# StormNet18-v0_1.net
KiCad netlist of a schematic drawn in EAGLE
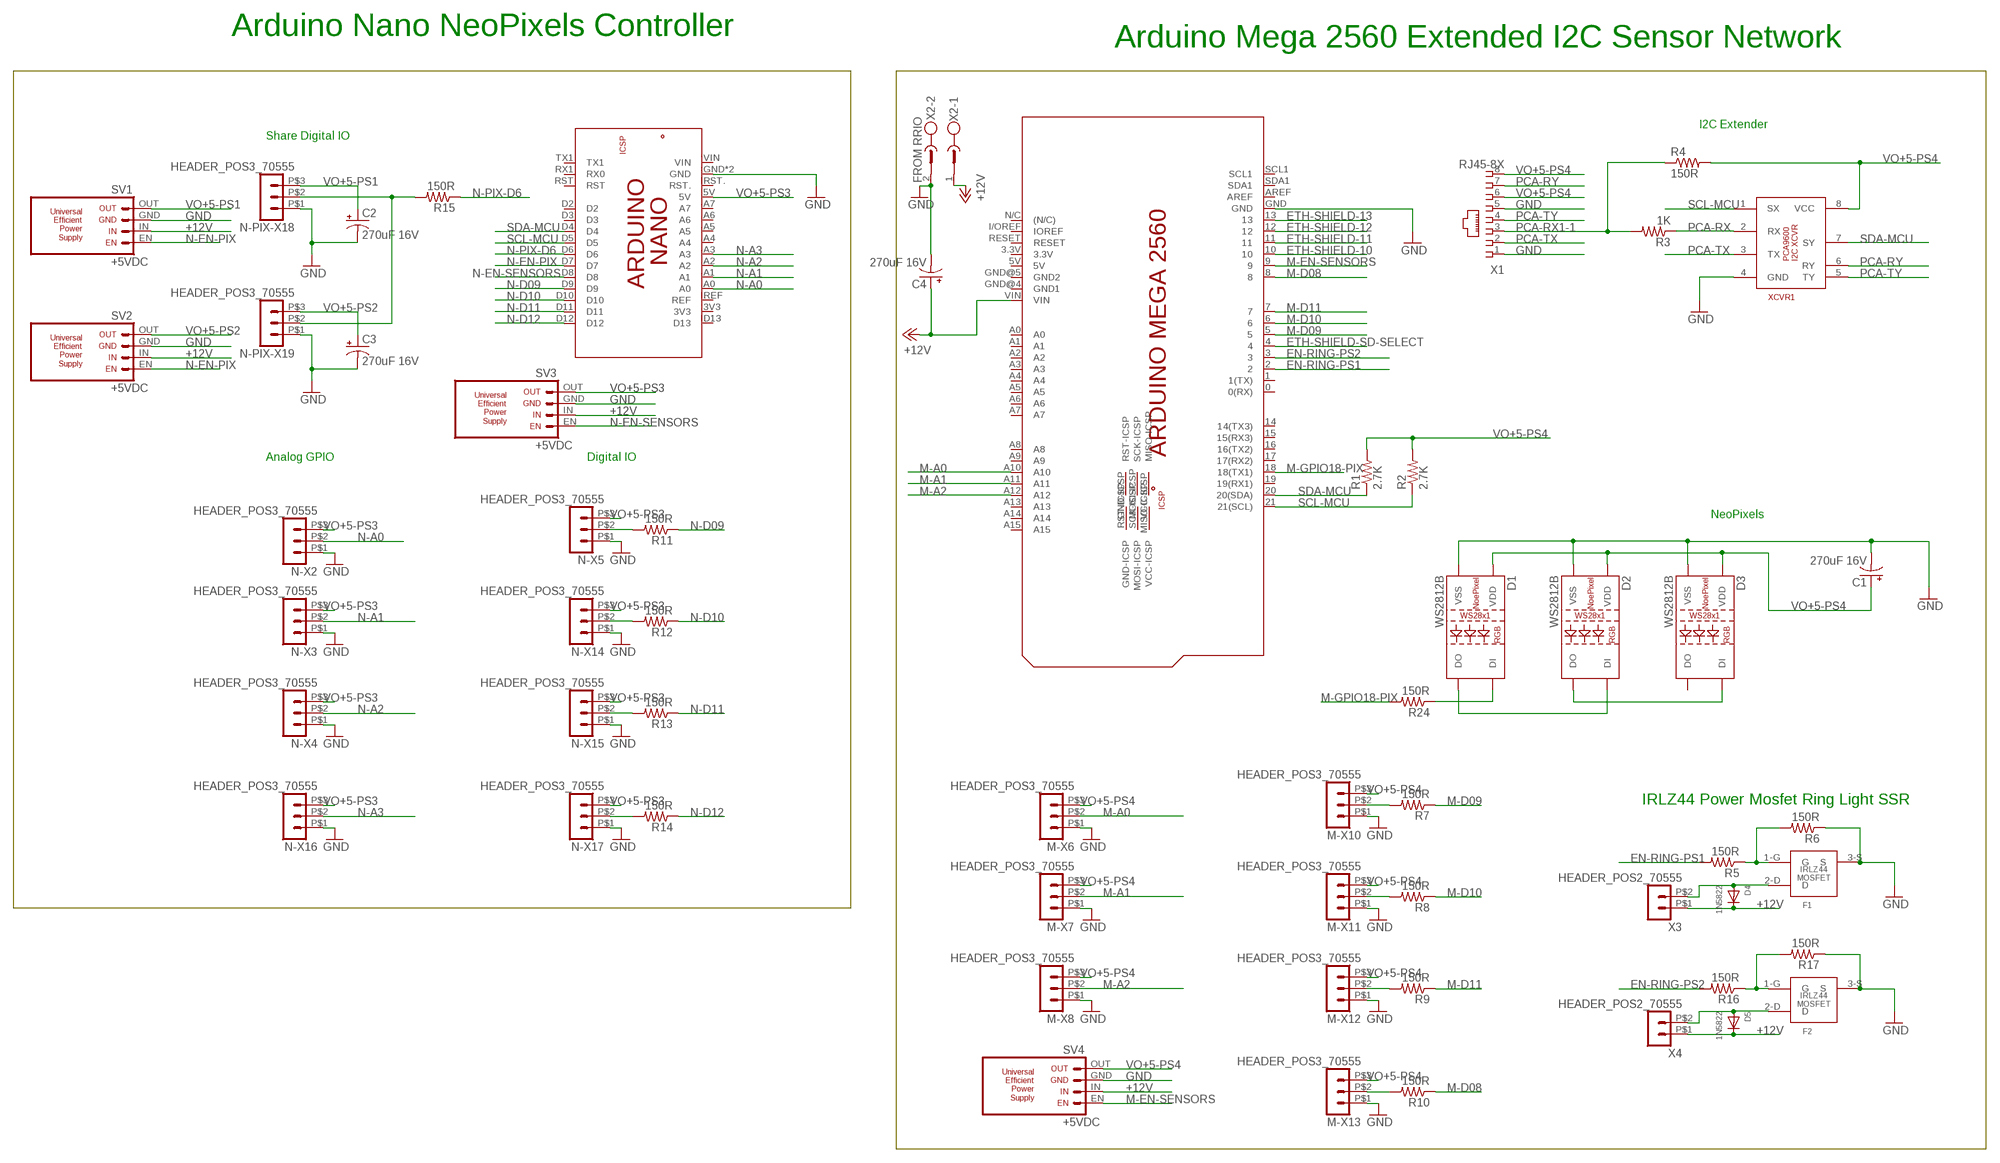
[diagram p0: schematic, sheet 1]

(export (version "E")
  (design (tool "Eeschema 10.0.6"))
  (components
    (comp (ref "C1")
      (value "270uF 16V")
      (footprint "eagle-import:E3,5-8")
      (libsource (lib "eagle-import") (part "CPOL-USE3.5-8"))
    )
    (comp (ref "C2")
      (value "270uF 16V")
      (footprint "eagle-import:E3,5-8")
      (libsource (lib "eagle-import") (part "CPOL-USE3.5-8"))
    )
    (comp (ref "C3")
      (value "270uF 16V")
      (footprint "eagle-import:E3,5-8")
      (libsource (lib "eagle-import") (part "CPOL-USE3.5-8"))
    )
    (comp (ref "C4")
      (value "270uF 16V")
      (footprint "eagle-import:E3,5-8")
      (libsource (lib "eagle-import") (part "CPOL-USE3.5-8"))
    )
    (comp (ref "D1")
      (value "WS2812B")
      (footprint "eagle-import:WS2812B")
      (libsource (lib "eagle-import") (part "WS2812B"))
    )
    (comp (ref "D2")
      (value "WS2812B")
      (footprint "eagle-import:WS2812B")
      (libsource (lib "eagle-import") (part "WS2812B"))
    )
    (comp (ref "D3")
      (value "WS2812B")
      (footprint "eagle-import:WS2812B")
      (libsource (lib "eagle-import") (part "WS2812B"))
    )
    (comp (ref "D4")
      (value "1N5822")
      (footprint "eagle-import:SMADIODE")
      (libsource (lib "eagle-import") (part "DIODESMA"))
    )
    (comp (ref "D5")
      (value "1N5822")
      (footprint "eagle-import:SMADIODE")
      (libsource (lib "eagle-import") (part "DIODESMA"))
    )
    (comp (ref "F1")
      (value "IRLZ44")
      (footprint "eagle-import:IRLZ44-TO220")
      (libsource (lib "eagle-import") (part "IRLZ44"))
    )
    (comp (ref "F2")
      (value "IRLZ44")
      (footprint "eagle-import:IRLZ44-TO220")
      (libsource (lib "eagle-import") (part "IRLZ44"))
    )
    (comp (ref "M-X6")
      (value "HEADER_POS3_70555")
      (footprint "eagle-import:70555-POS3")
      (libsource (lib "eagle-import") (part "HEADER_POS3_?70555"))
    )
    (comp (ref "M-X7")
      (value "HEADER_POS3_70555")
      (footprint "eagle-import:70555-POS3")
      (libsource (lib "eagle-import") (part "HEADER_POS3_?70555"))
    )
    (comp (ref "M-X8")
      (value "HEADER_POS3_70555")
      (footprint "eagle-import:70555-POS3")
      (libsource (lib "eagle-import") (part "HEADER_POS3_?70555"))
    )
    (comp (ref "M-X10")
      (value "HEADER_POS3_70555")
      (footprint "eagle-import:70555-POS3")
      (libsource (lib "eagle-import") (part "HEADER_POS3_?70555"))
    )
    (comp (ref "M-X11")
      (value "HEADER_POS3_70555")
      (footprint "eagle-import:70555-POS3")
      (libsource (lib "eagle-import") (part "HEADER_POS3_?70555"))
    )
    (comp (ref "M-X12")
      (value "HEADER_POS3_70555")
      (footprint "eagle-import:70555-POS3")
      (libsource (lib "eagle-import") (part "HEADER_POS3_?70555"))
    )
    (comp (ref "M-X13")
      (value "HEADER_POS3_70555")
      (footprint "eagle-import:70555-POS3")
      (libsource (lib "eagle-import") (part "HEADER_POS3_?70555"))
    )
    (comp (ref "N-PIX-X18")
      (value "HEADER_POS3_70555")
      (footprint "eagle-import:70555-POS3")
      (libsource (lib "eagle-import") (part "HEADER_POS3_?70555"))
    )
    (comp (ref "N-PIX-X19")
      (value "HEADER_POS3_70555")
      (footprint "eagle-import:70555-POS3")
      (libsource (lib "eagle-import") (part "HEADER_POS3_?70555"))
    )
    (comp (ref "N-X2")
      (value "HEADER_POS3_70555")
      (footprint "eagle-import:70555-POS3")
      (libsource (lib "eagle-import") (part "HEADER_POS3_?70555"))
    )
    (comp (ref "N-X3")
      (value "HEADER_POS3_70555")
      (footprint "eagle-import:70555-POS3")
      (libsource (lib "eagle-import") (part "HEADER_POS3_?70555"))
    )
    (comp (ref "N-X4")
      (value "HEADER_POS3_70555")
      (footprint "eagle-import:70555-POS3")
      (libsource (lib "eagle-import") (part "HEADER_POS3_?70555"))
    )
    (comp (ref "N-X5")
      (value "HEADER_POS3_70555")
      (footprint "eagle-import:70555-POS3")
      (libsource (lib "eagle-import") (part "HEADER_POS3_?70555"))
    )
    (comp (ref "N-X14")
      (value "HEADER_POS3_70555")
      (footprint "eagle-import:70555-POS3")
      (libsource (lib "eagle-import") (part "HEADER_POS3_?70555"))
    )
    (comp (ref "N-X15")
      (value "HEADER_POS3_70555")
      (footprint "eagle-import:70555-POS3")
      (libsource (lib "eagle-import") (part "HEADER_POS3_?70555"))
    )
    (comp (ref "N-X16")
      (value "HEADER_POS3_70555")
      (footprint "eagle-import:70555-POS3")
      (libsource (lib "eagle-import") (part "HEADER_POS3_?70555"))
    )
    (comp (ref "N-X17")
      (value "HEADER_POS3_70555")
      (footprint "eagle-import:70555-POS3")
      (libsource (lib "eagle-import") (part "HEADER_POS3_?70555"))
    )
    (comp (ref "PCB2")
      (value "ARDUINO_MEGA2560_SMALL")
      (footprint "eagle-import:ARDUINO_MEGA2560_SMALL")
      (libsource (lib "eagle-import") (part "ARDUINO_MEGA2560_SMALL"))
    )
    (comp (ref "PCB3")
      (value "ARDUINO_NANOWITHOUT_ICSP")
      (footprint "eagle-import:ARDUINO_NANO")
      (libsource (lib "eagle-import") (part "ARDUINO_NANOWITHOUT_ICSP"))
    )
    (comp (ref "R1")
      (value "2.7K")
      (footprint "eagle-import:R0603")
      (libsource (lib "eagle-import") (part "R-US_R0603"))
    )
    (comp (ref "R2")
      (value "2.7K")
      (footprint "eagle-import:R0603")
      (libsource (lib "eagle-import") (part "R-US_R0603"))
    )
    (comp (ref "R3")
      (value "1K")
      (footprint "eagle-import:R0603")
      (libsource (lib "eagle-import") (part "R-US_R0603"))
    )
    (comp (ref "R4")
      (value "150R")
      (footprint "eagle-import:R0603")
      (libsource (lib "eagle-import") (part "R-US_R0603"))
    )
    (comp (ref "R5")
      (value "150R")
      (footprint "eagle-import:R0603")
      (libsource (lib "eagle-import") (part "R-US_R0603"))
    )
    (comp (ref "R6")
      (value "150R")
      (footprint "eagle-import:R0603")
      (libsource (lib "eagle-import") (part "R-US_R0603"))
    )
    (comp (ref "R7")
      (value "150R")
      (footprint "eagle-import:R0603")
      (libsource (lib "eagle-import") (part "R-US_R0603"))
    )
    (comp (ref "R8")
      (value "150R")
      (footprint "eagle-import:R0603")
      (libsource (lib "eagle-import") (part "R-US_R0603"))
    )
    (comp (ref "R9")
      (value "150R")
      (footprint "eagle-import:R0603")
      (libsource (lib "eagle-import") (part "R-US_R0603"))
    )
    (comp (ref "R10")
      (value "150R")
      (footprint "eagle-import:R0603")
      (libsource (lib "eagle-import") (part "R-US_R0603"))
    )
    (comp (ref "R11")
      (value "150R")
      (footprint "eagle-import:R0603")
      (libsource (lib "eagle-import") (part "R-US_R0603"))
    )
    (comp (ref "R12")
      (value "150R")
      (footprint "eagle-import:R0603")
      (libsource (lib "eagle-import") (part "R-US_R0603"))
    )
    (comp (ref "R13")
      (value "150R")
      (footprint "eagle-import:R0603")
      (libsource (lib "eagle-import") (part "R-US_R0603"))
    )
    (comp (ref "R14")
      (value "150R")
      (footprint "eagle-import:R0603")
      (libsource (lib "eagle-import") (part "R-US_R0603"))
    )
    (comp (ref "R15")
      (value "150R")
      (footprint "eagle-import:R0603")
      (libsource (lib "eagle-import") (part "R-US_R0603"))
    )
    (comp (ref "R16")
      (value "150R")
      (footprint "eagle-import:R0603")
      (libsource (lib "eagle-import") (part "R-US_R0603"))
    )
    (comp (ref "R17")
      (value "150R")
      (footprint "eagle-import:R0603")
      (libsource (lib "eagle-import") (part "R-US_R0603"))
    )
    (comp (ref "R24")
      (value "150R")
      (footprint "eagle-import:R0603")
      (libsource (lib "eagle-import") (part "R-US_R0603"))
    )
    (comp (ref "SV1")
      (value "+5VDC")
      (footprint "eagle-import:PS-UNIV-EFFICIENT-3A")
      (libsource (lib "eagle-import") (part "SUPPLY-UNIV-EFFICIENT"))
    )
    (comp (ref "SV2")
      (value "+5VDC")
      (footprint "eagle-import:PS-UNIV-EFFICIENT-3A")
      (libsource (lib "eagle-import") (part "SUPPLY-UNIV-EFFICIENT"))
    )
    (comp (ref "SV3")
      (value "+5VDC")
      (footprint "eagle-import:PS-UNIV-EFFICIENT-3A")
      (libsource (lib "eagle-import") (part "SUPPLY-UNIV-EFFICIENT"))
    )
    (comp (ref "SV4")
      (value "+5VDC")
      (footprint "eagle-import:PS-UNIV-EFFICIENT-3A")
      (libsource (lib "eagle-import") (part "SUPPLY-UNIV-EFFICIENT"))
    )
    (comp (ref "X1")
      (value "RJ45-8X")
      (footprint "eagle-import:RJ45-NO-SHIELD")
      (libsource (lib "eagle-import") (part "RJ45-8X"))
    )
    (comp (ref "X2")
      (value "FROM RRIO")
      (footprint "eagle-import:MSTBV2-SMALL")
      (libsource (lib "eagle-import") (part "MSTBV2"))
    )
    (comp (ref "X3")
      (value "HEADER_POS2_70555")
      (footprint "eagle-import:70555-POS2")
      (libsource (lib "eagle-import") (part "HEADER_POS2_?70555"))
    )
    (comp (ref "X4")
      (value "HEADER_POS2_70555")
      (footprint "eagle-import:70555-POS2")
      (libsource (lib "eagle-import") (part "HEADER_POS2_?70555"))
    )
    (comp (ref "XCVR1")
      (value "PCA9600DSO8")
      (footprint "eagle-import:SO08")
      (libsource (lib "eagle-import") (part "PCA9600DSO8"))
    )
  )
  (nets
    (net (code "1") (name "+12V") (class "Default")
      (node (ref "C4") (pin "+") (pinfunction "+_+") (pintype "passive"))
      (node (ref "D4") (pin "C") (pinfunction "C_C") (pintype "passive"))
      (node (ref "D5") (pin "C") (pinfunction "C_C") (pintype "passive"))
      (node (ref "PCB2") (pin "VIN") (pinfunction "VIN_VIN") (pintype "power_in"))
      (node (ref "SV1") (pin "IN") (pinfunction "IN_IN") (pintype "passive"))
      (node (ref "SV2") (pin "IN") (pinfunction "IN_IN") (pintype "passive"))
      (node (ref "SV3") (pin "IN") (pinfunction "IN_IN") (pintype "passive"))
      (node (ref "SV4") (pin "IN") (pinfunction "IN_IN") (pintype "passive"))
      (node (ref "X2") (pin "1") (pinfunction "SK_1") (pintype "passive"))
      (node (ref "X3") (pin "P$1") (pinfunction "1_P$1") (pintype "passive"))
      (node (ref "X4") (pin "P$1") (pinfunction "1_P$1") (pintype "passive"))
    )
    (net (code "2") (name "/3.3V") (class "Default")
      (node (ref "PCB2") (pin "3.3V") (pinfunction "3.3V_3.3V") (pintype "power_in"))
    )
    (net (code "3") (name "/5V") (class "Default")
      (node (ref "PCB2") (pin "5V") (pinfunction "5V_5V") (pintype "power_in"))
    )
    (net (code "4") (name "/EN-RING-PS1") (class "Default")
      (node (ref "PCB2") (pin "2") (pinfunction "2_2") (pintype "bidirectional"))
      (node (ref "R5") (pin "2") (pinfunction "2_2") (pintype "passive"))
    )
    (net (code "5") (name "/EN-RING-PS2") (class "Default")
      (node (ref "PCB2") (pin "3") (pinfunction "3_3") (pintype "bidirectional"))
      (node (ref "R16") (pin "2") (pinfunction "2_2") (pintype "passive"))
    )
    (net (code "6") (name "/ETH-SHIELD-10") (class "Default")
      (node (ref "PCB2") (pin "10") (pinfunction "10_10") (pintype "bidirectional"))
    )
    (net (code "7") (name "/ETH-SHIELD-11") (class "Default")
      (node (ref "PCB2") (pin "11") (pinfunction "11_11") (pintype "bidirectional"))
    )
    (net (code "8") (name "/ETH-SHIELD-12") (class "Default")
      (node (ref "PCB2") (pin "12") (pinfunction "12_12") (pintype "bidirectional"))
    )
    (net (code "9") (name "/ETH-SHIELD-13") (class "Default")
      (node (ref "PCB2") (pin "13") (pinfunction "13_13") (pintype "bidirectional"))
    )
    (net (code "10") (name "/ETH-SHIELD-SD-SELECT") (class "Default")
      (node (ref "PCB2") (pin "4") (pinfunction "4_4") (pintype "bidirectional"))
    )
    (net (code "11") (name "/GND1") (class "Default")
      (node (ref "PCB2") (pin "GND@4") (pinfunction "GND1_GND@4") (pintype "power_in"))
    )
    (net (code "12") (name "/GND2") (class "Default")
      (node (ref "PCB2") (pin "GND@5") (pinfunction "GND2_GND@5") (pintype "power_in"))
    )
    (net (code "13") (name "/M-A0") (class "Default")
      (node (ref "M-X6") (pin "P$2") (pinfunction "2_P$2") (pintype "passive"))
      (node (ref "PCB2") (pin "A10") (pinfunction "A10_A10") (pintype "bidirectional"))
    )
    (net (code "14") (name "/M-A1") (class "Default")
      (node (ref "M-X7") (pin "P$2") (pinfunction "2_P$2") (pintype "passive"))
      (node (ref "PCB2") (pin "A11") (pinfunction "A11_A11") (pintype "bidirectional"))
    )
    (net (code "15") (name "/M-A2") (class "Default")
      (node (ref "M-X8") (pin "P$2") (pinfunction "2_P$2") (pintype "passive"))
      (node (ref "PCB2") (pin "A12") (pinfunction "A12_A12") (pintype "bidirectional"))
    )
    (net (code "16") (name "/M-D08") (class "Default")
      (node (ref "PCB2") (pin "8") (pinfunction "8_8") (pintype "bidirectional"))
      (node (ref "R10") (pin "1") (pinfunction "1_1") (pintype "passive"))
    )
    (net (code "17") (name "/M-D09") (class "Default")
      (node (ref "PCB2") (pin "5") (pinfunction "5_5") (pintype "bidirectional"))
      (node (ref "R7") (pin "1") (pinfunction "1_1") (pintype "passive"))
    )
    (net (code "18") (name "/M-D10") (class "Default")
      (node (ref "PCB2") (pin "6") (pinfunction "6_6") (pintype "bidirectional"))
      (node (ref "R8") (pin "1") (pinfunction "1_1") (pintype "passive"))
    )
    (net (code "19") (name "/M-D11") (class "Default")
      (node (ref "PCB2") (pin "7") (pinfunction "7_7") (pintype "bidirectional"))
      (node (ref "R9") (pin "1") (pinfunction "1_1") (pintype "passive"))
    )
    (net (code "20") (name "/M-EN-SENSORS") (class "Default")
      (node (ref "PCB2") (pin "9") (pinfunction "9_9") (pintype "bidirectional"))
      (node (ref "SV4") (pin "EN") (pinfunction "EN_EN") (pintype "passive"))
    )
    (net (code "21") (name "/M-GPIO18-PIX") (class "Default")
      (node (ref "PCB2") (pin "18") (pinfunction "18(TX1)_18") (pintype "bidirectional"))
      (node (ref "R24") (pin "2") (pinfunction "2_2") (pintype "passive"))
    )
    (net (code "22") (name "/N-A0") (class "Default")
      (node (ref "N-X2") (pin "P$2") (pinfunction "2_P$2") (pintype "passive"))
      (node (ref "PCB3") (pin "A0") (pinfunction "A0_A0") (pintype "bidirectional"))
    )
    (net (code "23") (name "/N-A1") (class "Default")
      (node (ref "N-X3") (pin "P$2") (pinfunction "2_P$2") (pintype "passive"))
      (node (ref "PCB3") (pin "A1") (pinfunction "A1_A1") (pintype "bidirectional"))
    )
    (net (code "24") (name "/N-A2") (class "Default")
      (node (ref "N-X4") (pin "P$2") (pinfunction "2_P$2") (pintype "passive"))
      (node (ref "PCB3") (pin "A2") (pinfunction "A2_A2") (pintype "bidirectional"))
    )
    (net (code "25") (name "/N-A3") (class "Default")
      (node (ref "N-X16") (pin "P$2") (pinfunction "2_P$2") (pintype "passive"))
      (node (ref "PCB3") (pin "A3") (pinfunction "A3_A3") (pintype "bidirectional"))
    )
    (net (code "26") (name "/N-D09") (class "Default")
      (node (ref "PCB3") (pin "D9") (pinfunction "D9_D9") (pintype "bidirectional"))
      (node (ref "R11") (pin "1") (pinfunction "1_1") (pintype "passive"))
    )
    (net (code "27") (name "/N-D10") (class "Default")
      (node (ref "PCB3") (pin "D10") (pinfunction "D10_D10") (pintype "bidirectional"))
      (node (ref "R12") (pin "1") (pinfunction "1_1") (pintype "passive"))
    )
    (net (code "28") (name "/N-D11") (class "Default")
      (node (ref "PCB3") (pin "D11") (pinfunction "D11_D11") (pintype "bidirectional"))
      (node (ref "R13") (pin "1") (pinfunction "1_1") (pintype "passive"))
    )
    (net (code "29") (name "/N-D12") (class "Default")
      (node (ref "PCB3") (pin "D12") (pinfunction "D12_D12") (pintype "bidirectional"))
      (node (ref "R14") (pin "1") (pinfunction "1_1") (pintype "passive"))
    )
    (net (code "30") (name "/N-EN-PIX") (class "Default")
      (node (ref "PCB3") (pin "D7") (pinfunction "D7_D7") (pintype "bidirectional"))
      (node (ref "SV1") (pin "EN") (pinfunction "EN_EN") (pintype "passive"))
      (node (ref "SV2") (pin "EN") (pinfunction "EN_EN") (pintype "passive"))
    )
    (net (code "31") (name "/N-EN-SENSORS") (class "Default")
      (node (ref "PCB3") (pin "D8") (pinfunction "D8_D8") (pintype "bidirectional"))
      (node (ref "SV3") (pin "EN") (pinfunction "EN_EN") (pintype "passive"))
    )
    (net (code "32") (name "/N-PIX-D6") (class "Default")
      (node (ref "PCB3") (pin "D6") (pinfunction "D6_D6") (pintype "bidirectional"))
      (node (ref "R15") (pin "1") (pinfunction "1_1") (pintype "passive"))
    )
    (net (code "33") (name "/PCA-RX") (class "Default")
      (node (ref "R3") (pin "1") (pinfunction "1_1") (pintype "passive"))
      (node (ref "XCVR1") (pin "2") (pinfunction "RX_2") (pintype "bidirectional"))
    )
    (net (code "34") (name "/PCA-RX1-1") (class "Default")
      (node (ref "R3") (pin "2") (pinfunction "2_2") (pintype "passive"))
      (node (ref "R4") (pin "1") (pinfunction "1_1") (pintype "passive"))
      (node (ref "X1") (pin "3") (pinfunction "3_3") (pintype "passive"))
    )
    (net (code "35") (name "/PCA-RY") (class "Default")
      (node (ref "X1") (pin "7") (pinfunction "7_7") (pintype "passive"))
      (node (ref "XCVR1") (pin "6") (pinfunction "RY_6") (pintype "bidirectional"))
    )
    (net (code "36") (name "/PCA-TX") (class "Default")
      (node (ref "X1") (pin "2") (pinfunction "2_2") (pintype "passive"))
      (node (ref "XCVR1") (pin "3") (pinfunction "TX_3") (pintype "bidirectional"))
    )
    (net (code "37") (name "/PCA-TY") (class "Default")
      (node (ref "X1") (pin "4") (pinfunction "4_4") (pintype "passive"))
      (node (ref "XCVR1") (pin "5") (pinfunction "TY_5") (pintype "bidirectional"))
    )
    (net (code "38") (name "/SCL-MCU") (class "Default")
      (node (ref "PCB2") (pin "21") (pinfunction "21(SCL)_21") (pintype "bidirectional"))
      (node (ref "PCB3") (pin "D5") (pinfunction "D5_D5") (pintype "bidirectional"))
      (node (ref "R2") (pin "1") (pinfunction "1_1") (pintype "passive"))
      (node (ref "XCVR1") (pin "1") (pinfunction "SX_1") (pintype "bidirectional"))
    )
    (net (code "39") (name "/SDA-MCU") (class "Default")
      (node (ref "PCB2") (pin "20") (pinfunction "20(SDA)_20") (pintype "bidirectional"))
      (node (ref "PCB3") (pin "D4") (pinfunction "D4_D4") (pintype "bidirectional"))
      (node (ref "R1") (pin "1") (pinfunction "1_1") (pintype "passive"))
      (node (ref "XCVR1") (pin "7") (pinfunction "SY_7") (pintype "bidirectional"))
    )
    (net (code "40") (name "/VO+5-PS1") (class "Default")
      (node (ref "C2") (pin "+") (pinfunction "+_+") (pintype "passive"))
      (node (ref "N-PIX-X18") (pin "P$3") (pinfunction "3_P$3") (pintype "passive"))
      (node (ref "SV1") (pin "OUT") (pinfunction "OUT_OUT") (pintype "passive"))
    )
    (net (code "41") (name "/VO+5-PS2") (class "Default")
      (node (ref "C3") (pin "+") (pinfunction "+_+") (pintype "passive"))
      (node (ref "N-PIX-X19") (pin "P$3") (pinfunction "3_P$3") (pintype "passive"))
      (node (ref "SV2") (pin "OUT") (pinfunction "OUT_OUT") (pintype "passive"))
    )
    (net (code "42") (name "/VO+5-PS3") (class "Default")
      (node (ref "N-X14") (pin "P$3") (pinfunction "3_P$3") (pintype "passive"))
      (node (ref "N-X15") (pin "P$3") (pinfunction "3_P$3") (pintype "passive"))
      (node (ref "N-X16") (pin "P$3") (pinfunction "3_P$3") (pintype "passive"))
      (node (ref "N-X17") (pin "P$3") (pinfunction "3_P$3") (pintype "passive"))
      (node (ref "N-X2") (pin "P$3") (pinfunction "3_P$3") (pintype "passive"))
      (node (ref "N-X3") (pin "P$3") (pinfunction "3_P$3") (pintype "passive"))
      (node (ref "N-X4") (pin "P$3") (pinfunction "3_P$3") (pintype "passive"))
      (node (ref "N-X5") (pin "P$3") (pinfunction "3_P$3") (pintype "passive"))
      (node (ref "PCB3") (pin "5V") (pinfunction "5V_5V") (pintype "bidirectional"))
      (node (ref "SV3") (pin "OUT") (pinfunction "OUT_OUT") (pintype "passive"))
    )
    (net (code "43") (name "/VO+5-PS4") (class "Default")
      (node (ref "C1") (pin "+") (pinfunction "+_+") (pintype "passive"))
      (node (ref "D1") (pin "1") (pinfunction "VDD_1") (pintype "bidirectional"))
      (node (ref "D2") (pin "1") (pinfunction "VDD_1") (pintype "bidirectional"))
      (node (ref "D3") (pin "1") (pinfunction "VDD_1") (pintype "bidirectional"))
      (node (ref "M-X10") (pin "P$3") (pinfunction "3_P$3") (pintype "passive"))
      (node (ref "M-X11") (pin "P$3") (pinfunction "3_P$3") (pintype "passive"))
      (node (ref "M-X12") (pin "P$3") (pinfunction "3_P$3") (pintype "passive"))
      (node (ref "M-X13") (pin "P$3") (pinfunction "3_P$3") (pintype "passive"))
      (node (ref "M-X6") (pin "P$3") (pinfunction "3_P$3") (pintype "passive"))
      (node (ref "M-X7") (pin "P$3") (pinfunction "3_P$3") (pintype "passive"))
      (node (ref "M-X8") (pin "P$3") (pinfunction "3_P$3") (pintype "passive"))
      (node (ref "R1") (pin "2") (pinfunction "2_2") (pintype "passive"))
      (node (ref "R2") (pin "2") (pinfunction "2_2") (pintype "passive"))
      (node (ref "R4") (pin "2") (pinfunction "2_2") (pintype "passive"))
      (node (ref "SV4") (pin "OUT") (pinfunction "OUT_OUT") (pintype "passive"))
      (node (ref "X1") (pin "6") (pinfunction "6_6") (pintype "passive"))
      (node (ref "X1") (pin "8") (pinfunction "8_8") (pintype "passive"))
      (node (ref "XCVR1") (pin "8") (pinfunction "VCC_8") (pintype "bidirectional"))
    )
    (net (code "44") (name "GND") (class "Default")
      (node (ref "C1") (pin "-") (pinfunction "-_-") (pintype "passive"))
      (node (ref "C2") (pin "-") (pinfunction "-_-") (pintype "passive"))
      (node (ref "C3") (pin "-") (pinfunction "-_-") (pintype "passive"))
      (node (ref "C4") (pin "-") (pinfunction "-_-") (pintype "passive"))
      (node (ref "D1") (pin "3") (pinfunction "VSS_3") (pintype "bidirectional"))
      (node (ref "D2") (pin "3") (pinfunction "VSS_3") (pintype "bidirectional"))
      (node (ref "D3") (pin "3") (pinfunction "VSS_3") (pintype "bidirectional"))
      (node (ref "F1") (pin "3-S") (pinfunction "S_3-S") (pintype "bidirectional"))
      (node (ref "F2") (pin "3-S") (pinfunction "S_3-S") (pintype "bidirectional"))
      (node (ref "M-X10") (pin "P$1") (pinfunction "1_P$1") (pintype "passive"))
      (node (ref "M-X11") (pin "P$1") (pinfunction "1_P$1") (pintype "passive"))
      (node (ref "M-X12") (pin "P$1") (pinfunction "1_P$1") (pintype "passive"))
      (node (ref "M-X13") (pin "P$1") (pinfunction "1_P$1") (pintype "passive"))
      (node (ref "M-X6") (pin "P$1") (pinfunction "1_P$1") (pintype "passive"))
      (node (ref "M-X7") (pin "P$1") (pinfunction "1_P$1") (pintype "passive"))
      (node (ref "M-X8") (pin "P$1") (pinfunction "1_P$1") (pintype "passive"))
      (node (ref "N-PIX-X18") (pin "P$1") (pinfunction "1_P$1") (pintype "passive"))
      (node (ref "N-PIX-X19") (pin "P$1") (pinfunction "1_P$1") (pintype "passive"))
      (node (ref "N-X14") (pin "P$1") (pinfunction "1_P$1") (pintype "passive"))
      (node (ref "N-X15") (pin "P$1") (pinfunction "1_P$1") (pintype "passive"))
      (node (ref "N-X16") (pin "P$1") (pinfunction "1_P$1") (pintype "passive"))
      (node (ref "N-X17") (pin "P$1") (pinfunction "1_P$1") (pintype "passive"))
      (node (ref "N-X2") (pin "P$1") (pinfunction "1_P$1") (pintype "passive"))
      (node (ref "N-X3") (pin "P$1") (pinfunction "1_P$1") (pintype "passive"))
      (node (ref "N-X4") (pin "P$1") (pinfunction "1_P$1") (pintype "passive"))
      (node (ref "N-X5") (pin "P$1") (pinfunction "1_P$1") (pintype "passive"))
      (node (ref "PCB2") (pin "GND") (pinfunction "GND_GND") (pintype "power_in"))
      (node (ref "PCB3") (pin "GND") (pinfunction "GND_GND") (pintype "bidirectional"))
      (node (ref "PCB3") (pin "GND@1") (pinfunction "GND_GND@1") (pintype "bidirectional"))
      (node (ref "R17") (pin "1") (pinfunction "1_1") (pintype "passive"))
      (node (ref "R6") (pin "1") (pinfunction "1_1") (pintype "passive"))
      (node (ref "SV1") (pin "GND") (pinfunction "GND_GND") (pintype "passive"))
      (node (ref "SV2") (pin "GND") (pinfunction "GND_GND") (pintype "passive"))
      (node (ref "SV3") (pin "GND") (pinfunction "GND_GND") (pintype "passive"))
      (node (ref "SV4") (pin "GND") (pinfunction "GND_GND") (pintype "passive"))
      (node (ref "X1") (pin "1") (pinfunction "1_1") (pintype "passive"))
      (node (ref "X1") (pin "5") (pinfunction "5_5") (pintype "passive"))
      (node (ref "X2") (pin "2") (pinfunction "SK_2") (pintype "passive"))
      (node (ref "XCVR1") (pin "4") (pinfunction "GND_4") (pintype "bidirectional"))
    )
    (net (code "45") (name "Net-(D1-DI)") (class "Default")
      (node (ref "D1") (pin "4") (pinfunction "DI_4") (pintype "bidirectional"))
      (node (ref "R24") (pin "1") (pinfunction "1_1") (pintype "passive"))
    )
    (net (code "46") (name "Net-(D1-DO)") (class "Default")
      (node (ref "D1") (pin "2") (pinfunction "DO_2") (pintype "bidirectional"))
      (node (ref "D2") (pin "4") (pinfunction "DI_4") (pintype "bidirectional"))
    )
    (net (code "47") (name "Net-(D2-DO)") (class "Default")
      (node (ref "D2") (pin "2") (pinfunction "DO_2") (pintype "bidirectional"))
      (node (ref "D3") (pin "4") (pinfunction "DI_4") (pintype "bidirectional"))
    )
    (net (code "48") (name "Net-(F1-D)") (class "Default")
      (node (ref "D4") (pin "A") (pinfunction "A_A") (pintype "passive"))
      (node (ref "F1") (pin "2-D") (pinfunction "D_2-D") (pintype "bidirectional"))
      (node (ref "X3") (pin "P$2") (pinfunction "2_P$2") (pintype "passive"))
    )
    (net (code "49") (name "Net-(F1-G)") (class "Default")
      (node (ref "F1") (pin "1-G") (pinfunction "G_1-G") (pintype "bidirectional"))
      (node (ref "R5") (pin "1") (pinfunction "1_1") (pintype "passive"))
      (node (ref "R6") (pin "2") (pinfunction "2_2") (pintype "passive"))
    )
    (net (code "50") (name "Net-(F2-D)") (class "Default")
      (node (ref "D5") (pin "A") (pinfunction "A_A") (pintype "passive"))
      (node (ref "F2") (pin "2-D") (pinfunction "D_2-D") (pintype "bidirectional"))
      (node (ref "X4") (pin "P$2") (pinfunction "2_P$2") (pintype "passive"))
    )
    (net (code "51") (name "Net-(F2-G)") (class "Default")
      (node (ref "F2") (pin "1-G") (pinfunction "G_1-G") (pintype "bidirectional"))
      (node (ref "R16") (pin "1") (pinfunction "1_1") (pintype "passive"))
      (node (ref "R17") (pin "2") (pinfunction "2_2") (pintype "passive"))
    )
    (net (code "52") (name "Net-(M-X10-2)") (class "Default")
      (node (ref "M-X10") (pin "P$2") (pinfunction "2_P$2") (pintype "passive"))
      (node (ref "R7") (pin "2") (pinfunction "2_2") (pintype "passive"))
    )
    (net (code "53") (name "Net-(M-X11-2)") (class "Default")
      (node (ref "M-X11") (pin "P$2") (pinfunction "2_P$2") (pintype "passive"))
      (node (ref "R8") (pin "2") (pinfunction "2_2") (pintype "passive"))
    )
    (net (code "54") (name "Net-(M-X12-2)") (class "Default")
      (node (ref "M-X12") (pin "P$2") (pinfunction "2_P$2") (pintype "passive"))
      (node (ref "R9") (pin "2") (pinfunction "2_2") (pintype "passive"))
    )
    (net (code "55") (name "Net-(M-X13-2)") (class "Default")
      (node (ref "M-X13") (pin "P$2") (pinfunction "2_P$2") (pintype "passive"))
      (node (ref "R10") (pin "2") (pinfunction "2_2") (pintype "passive"))
    )
    (net (code "56") (name "Net-(N-PIX-X18-2)") (class "Default")
      (node (ref "N-PIX-X18") (pin "P$2") (pinfunction "2_P$2") (pintype "passive"))
      (node (ref "N-PIX-X19") (pin "P$2") (pinfunction "2_P$2") (pintype "passive"))
      (node (ref "R15") (pin "2") (pinfunction "2_2") (pintype "passive"))
    )
    (net (code "57") (name "Net-(N-X5-2)") (class "Default")
      (node (ref "N-X5") (pin "P$2") (pinfunction "2_P$2") (pintype "passive"))
      (node (ref "R11") (pin "2") (pinfunction "2_2") (pintype "passive"))
    )
    (net (code "58") (name "Net-(N-X14-2)") (class "Default")
      (node (ref "N-X14") (pin "P$2") (pinfunction "2_P$2") (pintype "passive"))
      (node (ref "R12") (pin "2") (pinfunction "2_2") (pintype "passive"))
    )
    (net (code "59") (name "Net-(N-X15-2)") (class "Default")
      (node (ref "N-X15") (pin "P$2") (pinfunction "2_P$2") (pintype "passive"))
      (node (ref "R13") (pin "2") (pinfunction "2_2") (pintype "passive"))
    )
    (net (code "60") (name "Net-(N-X17-2)") (class "Default")
      (node (ref "N-X17") (pin "P$2") (pinfunction "2_P$2") (pintype "passive"))
      (node (ref "R14") (pin "2") (pinfunction "2_2") (pintype "passive"))
    )
    (net (code "61") (name "unconnected-(D3-DO-Pad2)") (class "Default")
      (node (ref "D3") (pin "2") (pinfunction "DO_2") (pintype "bidirectional"))
    )
    (net (code "62") (name "unconnected-(PCB2-(N{slash}C)-PadN{slash}C)") (class "Default")
      (node (ref "PCB2") (pin "N/C") (pinfunction "(N/C)_N/C") (pintype "no_connect"))
    )
    (net (code "63") (name "unconnected-(PCB2-0(RX)-Pad0)") (class "Default")
      (node (ref "PCB2") (pin "0") (pinfunction "0(RX)_0") (pintype "bidirectional"))
    )
    (net (code "64") (name "unconnected-(PCB2-1(TX)-Pad1)") (class "Default")
      (node (ref "PCB2") (pin "1") (pinfunction "1(TX)_1") (pintype "bidirectional"))
    )
    (net (code "65") (name "unconnected-(PCB2-14(TX3)-Pad14)") (class "Default")
      (node (ref "PCB2") (pin "14") (pinfunction "14(TX3)_14") (pintype "bidirectional"))
    )
    (net (code "66") (name "unconnected-(PCB2-15(RX3)-Pad15)") (class "Default")
      (node (ref "PCB2") (pin "15") (pinfunction "15(RX3)_15") (pintype "bidirectional"))
    )
    (net (code "67") (name "unconnected-(PCB2-16(TX2)-Pad16)") (class "Default")
      (node (ref "PCB2") (pin "16") (pinfunction "16(TX2)_16") (pintype "bidirectional"))
    )
    (net (code "68") (name "unconnected-(PCB2-17(RX2)-Pad17)") (class "Default")
      (node (ref "PCB2") (pin "17") (pinfunction "17(RX2)_17") (pintype "bidirectional"))
    )
    (net (code "69") (name "unconnected-(PCB2-19(RX1)-Pad19)") (class "Default")
      (node (ref "PCB2") (pin "19") (pinfunction "19(RX1)_19") (pintype "bidirectional"))
    )
    (net (code "70") (name "unconnected-(PCB2-IOREF-PadI{slash}OREF)") (class "Default")
      (node (ref "PCB2") (pin "I/OREF") (pinfunction "IOREF_I/OREF") (pintype "bidirectional"))
    )
    (net (code "71") (name "unconnected-(PCB2-PadA0)") (class "Default")
      (node (ref "PCB2") (pin "A0") (pinfunction "A0_A0") (pintype "bidirectional"))
    )
    (net (code "72") (name "unconnected-(PCB2-PadA1)") (class "Default")
      (node (ref "PCB2") (pin "A1") (pinfunction "A1_A1") (pintype "bidirectional"))
    )
    (net (code "73") (name "unconnected-(PCB2-PadA2)") (class "Default")
      (node (ref "PCB2") (pin "A2") (pinfunction "A2_A2") (pintype "bidirectional"))
    )
    (net (code "74") (name "unconnected-(PCB2-PadA3)") (class "Default")
      (node (ref "PCB2") (pin "A3") (pinfunction "A3_A3") (pintype "bidirectional"))
    )
    (net (code "75") (name "unconnected-(PCB2-PadA4)") (class "Default")
      (node (ref "PCB2") (pin "A4") (pinfunction "A4_A4") (pintype "bidirectional"))
    )
    (net (code "76") (name "unconnected-(PCB2-PadA5)") (class "Default")
      (node (ref "PCB2") (pin "A5") (pinfunction "A5_A5") (pintype "bidirectional"))
    )
    (net (code "77") (name "unconnected-(PCB2-PadA6)") (class "Default")
      (node (ref "PCB2") (pin "A6") (pinfunction "A6_A6") (pintype "bidirectional"))
    )
    (net (code "78") (name "unconnected-(PCB2-PadA7)") (class "Default")
      (node (ref "PCB2") (pin "A7") (pinfunction "A7_A7") (pintype "bidirectional"))
    )
    (net (code "79") (name "unconnected-(PCB2-PadA8)") (class "Default")
      (node (ref "PCB2") (pin "A8") (pinfunction "A8_A8") (pintype "bidirectional"))
    )
    (net (code "80") (name "unconnected-(PCB2-PadA9)") (class "Default")
      (node (ref "PCB2") (pin "A9") (pinfunction "A9_A9") (pintype "bidirectional"))
    )
    (net (code "81") (name "unconnected-(PCB2-PadA13)") (class "Default")
      (node (ref "PCB2") (pin "A13") (pinfunction "A13_A13") (pintype "bidirectional"))
    )
    (net (code "82") (name "unconnected-(PCB2-PadA14)") (class "Default")
      (node (ref "PCB2") (pin "A14") (pinfunction "A14_A14") (pintype "bidirectional"))
    )
    (net (code "83") (name "unconnected-(PCB2-PadA15)") (class "Default")
      (node (ref "PCB2") (pin "A15") (pinfunction "A15_A15") (pintype "bidirectional"))
    )
    (net (code "84") (name "unconnected-(PCB2-PadAREF)") (class "Default")
      (node (ref "PCB2") (pin "AREF") (pinfunction "AREF_AREF") (pintype "bidirectional"))
    )
    (net (code "85") (name "unconnected-(PCB2-PadGND-ICSP)") (class "Default")
      (node (ref "PCB2") (pin "GND-ICSP") (pinfunction "GND-ICSP_GND-ICSP") (pintype "bidirectional"))
    )
    (net (code "86") (name "unconnected-(PCB2-PadMISO-ICSP)") (class "Default")
      (node (ref "PCB2") (pin "MISO-ICSP") (pinfunction "MISO-ICSP_MISO-ICSP") (pintype "bidirectional"))
    )
    (net (code "87") (name "unconnected-(PCB2-PadMOSI-ICSP)") (class "Default")
      (node (ref "PCB2") (pin "MOSI-ICSP") (pinfunction "MOSI-ICSP_MOSI-ICSP") (pintype "bidirectional"))
    )
    (net (code "88") (name "unconnected-(PCB2-PadRESET)") (class "Default")
      (node (ref "PCB2") (pin "RESET") (pinfunction "RESET_RESET") (pintype "input"))
    )
    (net (code "89") (name "unconnected-(PCB2-PadRST-ICSP)") (class "Default")
      (node (ref "PCB2") (pin "RST-ICSP") (pinfunction "RST-ICSP_RST-ICSP") (pintype "bidirectional"))
    )
    (net (code "90") (name "unconnected-(PCB2-PadSCK-ICSP)") (class "Default")
      (node (ref "PCB2") (pin "SCK-ICSP") (pinfunction "SCK-ICSP_SCK-ICSP") (pintype "bidirectional"))
    )
    (net (code "91") (name "unconnected-(PCB2-PadSCL1)") (class "Default")
      (node (ref "PCB2") (pin "SCL1") (pinfunction "SCL1_SCL1") (pintype "bidirectional"))
    )
    (net (code "92") (name "unconnected-(PCB2-PadSDA1)") (class "Default")
      (node (ref "PCB2") (pin "SDA1") (pinfunction "SDA1_SDA1") (pintype "bidirectional"))
    )
    (net (code "93") (name "unconnected-(PCB2-PadVCC-ICSP)") (class "Default")
      (node (ref "PCB2") (pin "VCC-ICSP") (pinfunction "VCC-ICSP_VCC-ICSP") (pintype "bidirectional"))
    )
    (net (code "94") (name "unconnected-(PCB3-Pad3V3)") (class "Default")
      (node (ref "PCB3") (pin "3V3") (pinfunction "3V3_3V3") (pintype "bidirectional"))
    )
    (net (code "95") (name "unconnected-(PCB3-PadA4)") (class "Default")
      (node (ref "PCB3") (pin "A4") (pinfunction "A4_A4") (pintype "bidirectional"))
    )
    (net (code "96") (name "unconnected-(PCB3-PadA5)") (class "Default")
      (node (ref "PCB3") (pin "A5") (pinfunction "A5_A5") (pintype "bidirectional"))
    )
    (net (code "97") (name "unconnected-(PCB3-PadA6)") (class "Default")
      (node (ref "PCB3") (pin "A6") (pinfunction "A6_A6") (pintype "bidirectional"))
    )
    (net (code "98") (name "unconnected-(PCB3-PadA7)") (class "Default")
      (node (ref "PCB3") (pin "A7") (pinfunction "A7_A7") (pintype "bidirectional"))
    )
    (net (code "99") (name "unconnected-(PCB3-PadD2)") (class "Default")
      (node (ref "PCB3") (pin "D2") (pinfunction "D2_D2") (pintype "bidirectional"))
    )
    (net (code "100") (name "unconnected-(PCB3-PadD3)") (class "Default")
      (node (ref "PCB3") (pin "D3") (pinfunction "D3_D3") (pintype "bidirectional"))
    )
    (net (code "101") (name "unconnected-(PCB3-PadD13)") (class "Default")
      (node (ref "PCB3") (pin "D13") (pinfunction "D13_D13") (pintype "bidirectional"))
    )
    (net (code "102") (name "unconnected-(PCB3-PadREF)") (class "Default")
      (node (ref "PCB3") (pin "REF") (pinfunction "REF_REF") (pintype "bidirectional"))
    )
    (net (code "103") (name "unconnected-(PCB3-PadRST)") (class "Default")
      (node (ref "PCB3") (pin "RST") (pinfunction "RST_RST") (pintype "bidirectional"))
    )
    (net (code "104") (name "unconnected-(PCB3-PadRST.)") (class "Default")
      (node (ref "PCB3") (pin "RST.") (pinfunction "RST._RST.") (pintype "bidirectional"))
    )
    (net (code "105") (name "unconnected-(PCB3-PadTX1)") (class "Default")
      (node (ref "PCB3") (pin "TX1") (pinfunction "TX1_TX1") (pintype "bidirectional"))
    )
    (net (code "106") (name "unconnected-(PCB3-PadVIN)") (class "Default")
      (node (ref "PCB3") (pin "VIN") (pinfunction "VIN_VIN") (pintype "bidirectional"))
    )
    (net (code "107") (name "unconnected-(PCB3-RX0-PadRX1)") (class "Default")
      (node (ref "PCB3") (pin "RX1") (pinfunction "RX0_RX1") (pintype "bidirectional"))
    )
  )
)
